# Voltmetr_MEZ.net
KiCad netlist of a schematic drawn in Altium Designer
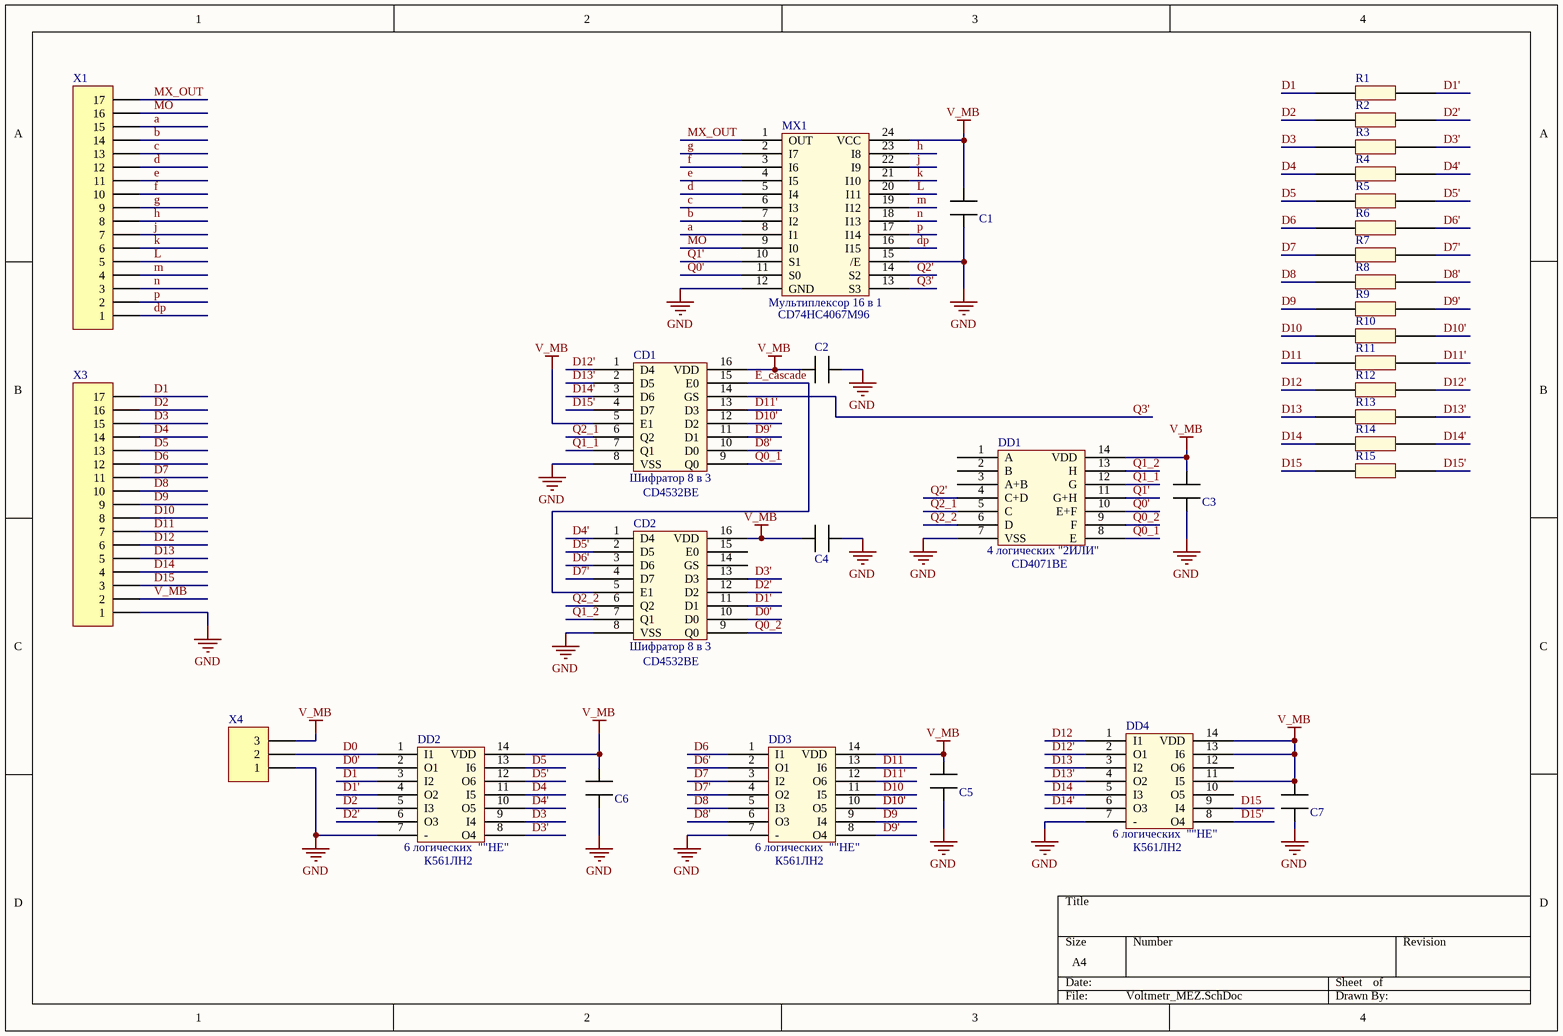
[diagram p0: Voltmetr_MEZ.SchDoc]

(export (version "E")
  (design (tool "Eeschema 10.0.6"))
  (components
    (comp (ref "C1")
      (value "CAP_SMALL")
      (footprint "CAP_SMALL")
      (libsource (lib "vpl_Schlib") (part "CAP_SMALL"))
    )
    (comp (ref "C2")
      (value "CAP_SMALL")
      (footprint "CAP_SMALL")
      (libsource (lib "vpl_Schlib") (part "CAP_SMALL"))
    )
    (comp (ref "C3")
      (value "CAP_SMALL")
      (footprint "CAP_SMALL")
      (libsource (lib "vpl_Schlib") (part "CAP_SMALL"))
    )
    (comp (ref "C4")
      (value "CAP_SMALL")
      (footprint "CAP_SMALL")
      (libsource (lib "vpl_Schlib") (part "CAP_SMALL"))
    )
    (comp (ref "C5")
      (value "CAP_SMALL")
      (footprint "CAP_SMALL")
      (libsource (lib "vpl_Schlib") (part "CAP_SMALL"))
    )
    (comp (ref "C6")
      (value "CAP_SMALL")
      (footprint "CAP_SMALL")
      (libsource (lib "vpl_Schlib") (part "CAP_SMALL"))
    )
    (comp (ref "C7")
      (value "CAP_SMALL")
      (footprint "CAP_SMALL")
      (libsource (lib "vpl_Schlib") (part "CAP_SMALL"))
    )
    (comp (ref "CD1")
      (value "CD4532BE")
      (footprint "DIP16_PANNEL")
      (description "Шифратор приоритетный 8 - 3 [DIP-16]")
      (libsource (lib "msp_SchLib") (part "CD4532BE"))
    )
    (comp (ref "CD2")
      (value "CD4532BE")
      (footprint "DIP16_PANNEL")
      (description "Шифратор приоритетный 8 - 3 [DIP-16]")
      (libsource (lib "msp_SchLib") (part "CD4532BE"))
    )
    (comp (ref "DD1")
      (value "CD4071BE")
      (footprint "Dip14_pannel")
      (description "Четыре логических элемента \"2ИЛИ\", [DIP-14]")
      (libsource (lib "msp_SchLib") (part "CD4071BE"))
    )
    (comp (ref "DD2")
      (value "К561ЛН2")
      (footprint "Dip14_pannel")
      (description "Шесть логических элементов \"HЕ\" (DIP-14)")
      (libsource (lib "msp_SchLib") (part "К561ЛН2"))
    )
    (comp (ref "DD3")
      (value "К561ЛН2")
      (footprint "Dip14_pannel")
      (description "Шесть логических элементов \"HЕ\" (DIP-14)")
      (libsource (lib "msp_SchLib") (part "К561ЛН2"))
    )
    (comp (ref "DD4")
      (value "К561ЛН2")
      (footprint "Dip14_pannel")
      (description "Шесть логических элементов \"HЕ\" (DIP-14)")
      (libsource (lib "msp_SchLib") (part "К561ЛН2"))
    )
    (comp (ref "MX1")
      (value "CD74HC4067M96")
      (footprint "SOIC-24")
      (description "16-и канальный аналоговый мультиплексор/ демультиплексор, [SO-24]")
      (libsource (lib "msp_SchLib") (part "CD74HC4067M96"))
    )
    (comp (ref "R1") (value "resistor") (footprint "RES 0805") (libsource (lib "msp_SchLib") (part "RES")))
    (comp (ref "R2") (value "resistor") (footprint "RES 0805") (libsource (lib "msp_SchLib") (part "RES")))
    (comp (ref "R3") (value "resistor") (footprint "RES 0805") (libsource (lib "msp_SchLib") (part "RES")))
    (comp (ref "R4") (value "resistor") (footprint "RES 0805") (libsource (lib "msp_SchLib") (part "RES")))
    (comp (ref "R5") (value "resistor") (footprint "RES 0805") (libsource (lib "msp_SchLib") (part "RES")))
    (comp (ref "R6") (value "resistor") (footprint "RES 0805") (libsource (lib "msp_SchLib") (part "RES")))
    (comp (ref "R7") (value "resistor") (footprint "RES 0805") (libsource (lib "msp_SchLib") (part "RES")))
    (comp (ref "R8") (value "resistor") (footprint "RES 0805") (libsource (lib "msp_SchLib") (part "RES")))
    (comp (ref "R9") (value "resistor") (footprint "RES 0805") (libsource (lib "msp_SchLib") (part "RES")))
    (comp (ref "R10") (value "resistor") (footprint "RES 0805") (libsource (lib "msp_SchLib") (part "RES")))
    (comp (ref "R11") (value "resistor") (footprint "RES 0805") (libsource (lib "msp_SchLib") (part "RES")))
    (comp (ref "R12") (value "resistor") (footprint "RES 0805") (libsource (lib "msp_SchLib") (part "RES")))
    (comp (ref "R13") (value "resistor") (footprint "RES 0805") (libsource (lib "msp_SchLib") (part "RES")))
    (comp (ref "R14") (value "resistor") (footprint "RES 0805") (libsource (lib "msp_SchLib") (part "RES")))
    (comp (ref "R15") (value "resistor") (footprint "RES 0805") (libsource (lib "msp_SchLib") (part "RES")))
    (comp (ref "X1")
      (value "Header 17")
      (footprint "HDR1X17")
      (description "Header, 17-Pin")
      (fields (field (name "PUBLISHER") "Altium Limited"))
      (libsource (lib "Miscellaneous Connectors") (part "Header 17"))
    )
    (comp (ref "X3")
      (value "Header 17")
      (footprint "HDR1X17")
      (description "Header, 17-Pin")
      (fields (field (name "PUBLISHER") "Altium Limited"))
      (libsource (lib "Miscellaneous Connectors") (part "Header 17"))
    )
    (comp (ref "X4")
      (value "Header 3")
      (footprint "HDR1X3")
      (description "Header, 3-Pin")
      (fields (field (name "PUBLISHER") "Altium Limited"))
      (libsource (lib "Miscellaneous Connectors") (part "Header 3"))
    )
  )
  (nets
    (net (code "2") (name "/D0") (class "Default")
      (node (ref "DD2") (pin "1") (pinfunction "I1_1") (pintype "passive"))
      (node (ref "X4") (pin "2") (pinfunction "2_2") (pintype "passive"))
    )
    (net (code "3") (name "/D0'") (class "Default")
      (node (ref "CD2") (pin "10") (pinfunction "D0_10") (pintype "passive"))
      (node (ref "DD2") (pin "2") (pinfunction "O1_2") (pintype "passive"))
    )
    (net (code "4") (name "/D1") (class "Default")
      (node (ref "DD2") (pin "3") (pinfunction "I2_3") (pintype "passive"))
      (node (ref "R1") (pin "1") (pinfunction "1_1") (pintype "passive"))
      (node (ref "X3") (pin "17") (pinfunction "17_17") (pintype "passive"))
    )
    (net (code "5") (name "/D1'") (class "Default")
      (node (ref "CD2") (pin "11") (pinfunction "D1_11") (pintype "passive"))
      (node (ref "DD2") (pin "4") (pinfunction "O2_4") (pintype "passive"))
      (node (ref "R1") (pin "2") (pinfunction "2_2") (pintype "passive"))
    )
    (net (code "6") (name "/D2") (class "Default")
      (node (ref "DD2") (pin "5") (pinfunction "I3_5") (pintype "passive"))
      (node (ref "R2") (pin "1") (pinfunction "1_1") (pintype "passive"))
      (node (ref "X3") (pin "16") (pinfunction "16_16") (pintype "passive"))
    )
    (net (code "7") (name "/D2'") (class "Default")
      (node (ref "CD2") (pin "12") (pinfunction "D2_12") (pintype "passive"))
      (node (ref "DD2") (pin "6") (pinfunction "O3_6") (pintype "passive"))
      (node (ref "R2") (pin "2") (pinfunction "2_2") (pintype "passive"))
    )
    (net (code "8") (name "/D3") (class "Default")
      (node (ref "DD2") (pin "9") (pinfunction "I4_9") (pintype "passive"))
      (node (ref "R3") (pin "1") (pinfunction "1_1") (pintype "passive"))
      (node (ref "X3") (pin "15") (pinfunction "15_15") (pintype "passive"))
    )
    (net (code "9") (name "/D3'") (class "Default")
      (node (ref "CD2") (pin "13") (pinfunction "D3_13") (pintype "passive"))
      (node (ref "DD2") (pin "8") (pinfunction "O4_8") (pintype "passive"))
      (node (ref "R3") (pin "2") (pinfunction "2_2") (pintype "passive"))
    )
    (net (code "10") (name "/D4") (class "Default")
      (node (ref "DD2") (pin "11") (pinfunction "I5_11") (pintype "passive"))
      (node (ref "R4") (pin "1") (pinfunction "1_1") (pintype "passive"))
      (node (ref "X3") (pin "14") (pinfunction "14_14") (pintype "passive"))
    )
    (net (code "11") (name "/D4'") (class "Default")
      (node (ref "CD2") (pin "1") (pinfunction "D4_1") (pintype "passive"))
      (node (ref "DD2") (pin "10") (pinfunction "O5_10") (pintype "passive"))
      (node (ref "R4") (pin "2") (pinfunction "2_2") (pintype "passive"))
    )
    (net (code "12") (name "/D5") (class "Default")
      (node (ref "DD2") (pin "13") (pinfunction "I6_13") (pintype "passive"))
      (node (ref "R5") (pin "1") (pinfunction "1_1") (pintype "passive"))
      (node (ref "X3") (pin "13") (pinfunction "13_13") (pintype "passive"))
    )
    (net (code "13") (name "/D5'") (class "Default")
      (node (ref "CD2") (pin "2") (pinfunction "D5_2") (pintype "passive"))
      (node (ref "DD2") (pin "12") (pinfunction "O6_12") (pintype "passive"))
      (node (ref "R5") (pin "2") (pinfunction "2_2") (pintype "passive"))
    )
    (net (code "14") (name "/D6") (class "Default")
      (node (ref "DD3") (pin "1") (pinfunction "I1_1") (pintype "passive"))
      (node (ref "R6") (pin "1") (pinfunction "1_1") (pintype "passive"))
      (node (ref "X3") (pin "12") (pinfunction "12_12") (pintype "passive"))
    )
    (net (code "15") (name "/D6'") (class "Default")
      (node (ref "CD2") (pin "3") (pinfunction "D6_3") (pintype "passive"))
      (node (ref "DD3") (pin "2") (pinfunction "O1_2") (pintype "passive"))
      (node (ref "R6") (pin "2") (pinfunction "2_2") (pintype "passive"))
    )
    (net (code "16") (name "/D7") (class "Default")
      (node (ref "DD3") (pin "3") (pinfunction "I2_3") (pintype "passive"))
      (node (ref "R7") (pin "1") (pinfunction "1_1") (pintype "passive"))
      (node (ref "X3") (pin "11") (pinfunction "11_11") (pintype "passive"))
    )
    (net (code "17") (name "/D7'") (class "Default")
      (node (ref "CD2") (pin "4") (pinfunction "D7_4") (pintype "passive"))
      (node (ref "DD3") (pin "4") (pinfunction "O2_4") (pintype "passive"))
      (node (ref "R7") (pin "2") (pinfunction "2_2") (pintype "passive"))
    )
    (net (code "18") (name "/D8") (class "Default")
      (node (ref "DD3") (pin "5") (pinfunction "I3_5") (pintype "passive"))
      (node (ref "R8") (pin "1") (pinfunction "1_1") (pintype "passive"))
      (node (ref "X3") (pin "10") (pinfunction "10_10") (pintype "passive"))
    )
    (net (code "19") (name "/D8'") (class "Default")
      (node (ref "CD1") (pin "10") (pinfunction "D0_10") (pintype "passive"))
      (node (ref "DD3") (pin "6") (pinfunction "O3_6") (pintype "passive"))
      (node (ref "R8") (pin "2") (pinfunction "2_2") (pintype "passive"))
    )
    (net (code "20") (name "/D9") (class "Default")
      (node (ref "DD3") (pin "9") (pinfunction "I4_9") (pintype "passive"))
      (node (ref "R9") (pin "1") (pinfunction "1_1") (pintype "passive"))
      (node (ref "X3") (pin "9") (pinfunction "9_9") (pintype "passive"))
    )
    (net (code "21") (name "/D9'") (class "Default")
      (node (ref "CD1") (pin "11") (pinfunction "D1_11") (pintype "passive"))
      (node (ref "DD3") (pin "8") (pinfunction "O4_8") (pintype "passive"))
      (node (ref "R9") (pin "2") (pinfunction "2_2") (pintype "passive"))
    )
    (net (code "22") (name "/D10") (class "Default")
      (node (ref "DD3") (pin "11") (pinfunction "I5_11") (pintype "passive"))
      (node (ref "R10") (pin "1") (pinfunction "1_1") (pintype "passive"))
      (node (ref "X3") (pin "8") (pinfunction "8_8") (pintype "passive"))
    )
    (net (code "23") (name "/D10'") (class "Default")
      (node (ref "CD1") (pin "12") (pinfunction "D2_12") (pintype "passive"))
      (node (ref "DD3") (pin "10") (pinfunction "O5_10") (pintype "passive"))
      (node (ref "R10") (pin "2") (pinfunction "2_2") (pintype "passive"))
    )
    (net (code "24") (name "/D11") (class "Default")
      (node (ref "DD3") (pin "13") (pinfunction "I6_13") (pintype "passive"))
      (node (ref "R11") (pin "1") (pinfunction "1_1") (pintype "passive"))
      (node (ref "X3") (pin "7") (pinfunction "7_7") (pintype "passive"))
    )
    (net (code "25") (name "/D11'") (class "Default")
      (node (ref "CD1") (pin "13") (pinfunction "D3_13") (pintype "passive"))
      (node (ref "DD3") (pin "12") (pinfunction "O6_12") (pintype "passive"))
      (node (ref "R11") (pin "2") (pinfunction "2_2") (pintype "passive"))
    )
    (net (code "26") (name "/D12") (class "Default")
      (node (ref "DD4") (pin "1") (pinfunction "I1_1") (pintype "passive"))
      (node (ref "R12") (pin "1") (pinfunction "1_1") (pintype "passive"))
      (node (ref "X3") (pin "6") (pinfunction "6_6") (pintype "passive"))
    )
    (net (code "27") (name "/D12'") (class "Default")
      (node (ref "CD1") (pin "1") (pinfunction "D4_1") (pintype "passive"))
      (node (ref "DD4") (pin "2") (pinfunction "O1_2") (pintype "passive"))
      (node (ref "R12") (pin "2") (pinfunction "2_2") (pintype "passive"))
    )
    (net (code "28") (name "/D13") (class "Default")
      (node (ref "DD4") (pin "3") (pinfunction "I2_3") (pintype "passive"))
      (node (ref "R13") (pin "1") (pinfunction "1_1") (pintype "passive"))
      (node (ref "X3") (pin "5") (pinfunction "5_5") (pintype "passive"))
    )
    (net (code "29") (name "/D13'") (class "Default")
      (node (ref "CD1") (pin "2") (pinfunction "D5_2") (pintype "passive"))
      (node (ref "DD4") (pin "4") (pinfunction "O2_4") (pintype "passive"))
      (node (ref "R13") (pin "2") (pinfunction "2_2") (pintype "passive"))
    )
    (net (code "30") (name "/D14") (class "Default")
      (node (ref "DD4") (pin "5") (pinfunction "I3_5") (pintype "passive"))
      (node (ref "R14") (pin "1") (pinfunction "1_1") (pintype "passive"))
      (node (ref "X3") (pin "4") (pinfunction "4_4") (pintype "passive"))
    )
    (net (code "31") (name "/D14'") (class "Default")
      (node (ref "CD1") (pin "3") (pinfunction "D6_3") (pintype "passive"))
      (node (ref "DD4") (pin "6") (pinfunction "O3_6") (pintype "passive"))
      (node (ref "R14") (pin "2") (pinfunction "2_2") (pintype "passive"))
    )
    (net (code "32") (name "/D15") (class "Default")
      (node (ref "DD4") (pin "9") (pinfunction "I4_9") (pintype "passive"))
      (node (ref "R15") (pin "1") (pinfunction "1_1") (pintype "passive"))
      (node (ref "X3") (pin "3") (pinfunction "3_3") (pintype "passive"))
    )
    (net (code "33") (name "/D15'") (class "Default")
      (node (ref "CD1") (pin "4") (pinfunction "D7_4") (pintype "passive"))
      (node (ref "DD4") (pin "8") (pinfunction "O4_8") (pintype "passive"))
      (node (ref "R15") (pin "2") (pinfunction "2_2") (pintype "passive"))
    )
    (net (code "34") (name "/E_cascade") (class "Default")
      (node (ref "CD1") (pin "15") (pinfunction "E0_15") (pintype "passive"))
      (node (ref "CD2") (pin "5") (pinfunction "E1_5") (pintype "passive"))
    )
    (net (code "35") (name "/L") (class "Default")
      (node (ref "MX1") (pin "20") (pinfunction "I11_20") (pintype "passive"))
      (node (ref "X1") (pin "5") (pinfunction "5_5") (pintype "passive"))
    )
    (net (code "36") (name "/MX_OUT") (class "Default")
      (node (ref "MX1") (pin "1") (pinfunction "OUT_1") (pintype "passive"))
      (node (ref "X1") (pin "17") (pinfunction "17_17") (pintype "passive"))
    )
    (net (code "37") (name "/Q0'") (class "Default")
      (node (ref "DD1") (pin "10") (pinfunction "E+F_10") (pintype "passive"))
      (node (ref "MX1") (pin "11") (pinfunction "S0_11") (pintype "passive"))
    )
    (net (code "38") (name "/Q0_1") (class "Default")
      (node (ref "CD1") (pin "9") (pinfunction "Q0_9") (pintype "passive"))
      (node (ref "DD1") (pin "8") (pinfunction "E_8") (pintype "passive"))
    )
    (net (code "39") (name "/Q0_2") (class "Default")
      (node (ref "CD2") (pin "9") (pinfunction "Q0_9") (pintype "passive"))
      (node (ref "DD1") (pin "9") (pinfunction "F_9") (pintype "passive"))
    )
    (net (code "40") (name "/Q1'") (class "Default")
      (node (ref "DD1") (pin "11") (pinfunction "G+H_11") (pintype "passive"))
      (node (ref "MX1") (pin "10") (pinfunction "S1_10") (pintype "passive"))
    )
    (net (code "41") (name "/Q1_1") (class "Default")
      (node (ref "CD1") (pin "7") (pinfunction "Q1_7") (pintype "passive"))
      (node (ref "DD1") (pin "12") (pinfunction "G_12") (pintype "passive"))
    )
    (net (code "42") (name "/Q1_2") (class "Default")
      (node (ref "CD2") (pin "7") (pinfunction "Q1_7") (pintype "passive"))
      (node (ref "DD1") (pin "13") (pinfunction "H_13") (pintype "passive"))
    )
    (net (code "43") (name "/Q2'") (class "Default")
      (node (ref "DD1") (pin "4") (pinfunction "C+D_4") (pintype "passive"))
      (node (ref "MX1") (pin "14") (pinfunction "S2_14") (pintype "passive"))
    )
    (net (code "44") (name "/Q2_1") (class "Default")
      (node (ref "CD1") (pin "6") (pinfunction "Q2_6") (pintype "passive"))
      (node (ref "DD1") (pin "5") (pinfunction "C_5") (pintype "passive"))
    )
    (net (code "45") (name "/Q2_2") (class "Default")
      (node (ref "CD2") (pin "6") (pinfunction "Q2_6") (pintype "passive"))
      (node (ref "DD1") (pin "6") (pinfunction "D_6") (pintype "passive"))
    )
    (net (code "46") (name "/Q3'") (class "Default")
      (node (ref "CD1") (pin "14") (pinfunction "GS_14") (pintype "passive"))
      (node (ref "MX1") (pin "13") (pinfunction "S3_13") (pintype "passive"))
    )
    (net (code "47") (name "/a") (class "Default")
      (node (ref "MX1") (pin "8") (pinfunction "I1_8") (pintype "passive"))
      (node (ref "X1") (pin "15") (pinfunction "15_15") (pintype "passive"))
    )
    (net (code "48") (name "/b") (class "Default")
      (node (ref "MX1") (pin "7") (pinfunction "I2_7") (pintype "passive"))
      (node (ref "X1") (pin "14") (pinfunction "14_14") (pintype "passive"))
    )
    (net (code "49") (name "/c") (class "Default")
      (node (ref "MX1") (pin "6") (pinfunction "I3_6") (pintype "passive"))
      (node (ref "X1") (pin "13") (pinfunction "13_13") (pintype "passive"))
    )
    (net (code "50") (name "/d") (class "Default")
      (node (ref "MX1") (pin "5") (pinfunction "I4_5") (pintype "passive"))
      (node (ref "X1") (pin "12") (pinfunction "12_12") (pintype "passive"))
    )
    (net (code "51") (name "/dp") (class "Default")
      (node (ref "MX1") (pin "16") (pinfunction "I15_16") (pintype "passive"))
      (node (ref "X1") (pin "1") (pinfunction "1_1") (pintype "passive"))
    )
    (net (code "52") (name "/e") (class "Default")
      (node (ref "MX1") (pin "4") (pinfunction "I5_4") (pintype "passive"))
      (node (ref "X1") (pin "11") (pinfunction "11_11") (pintype "passive"))
    )
    (net (code "53") (name "/f") (class "Default")
      (node (ref "MX1") (pin "3") (pinfunction "I6_3") (pintype "passive"))
      (node (ref "X1") (pin "10") (pinfunction "10_10") (pintype "passive"))
    )
    (net (code "54") (name "/g") (class "Default")
      (node (ref "MX1") (pin "2") (pinfunction "I7_2") (pintype "passive"))
      (node (ref "X1") (pin "9") (pinfunction "9_9") (pintype "passive"))
    )
    (net (code "55") (name "/h") (class "Default")
      (node (ref "MX1") (pin "23") (pinfunction "I8_23") (pintype "passive"))
      (node (ref "X1") (pin "8") (pinfunction "8_8") (pintype "passive"))
    )
    (net (code "56") (name "/j") (class "Default")
      (node (ref "MX1") (pin "22") (pinfunction "I9_22") (pintype "passive"))
      (node (ref "X1") (pin "7") (pinfunction "7_7") (pintype "passive"))
    )
    (net (code "57") (name "/k") (class "Default")
      (node (ref "MX1") (pin "21") (pinfunction "I10_21") (pintype "passive"))
      (node (ref "X1") (pin "6") (pinfunction "6_6") (pintype "passive"))
    )
    (net (code "58") (name "/m") (class "Default")
      (node (ref "MX1") (pin "19") (pinfunction "I12_19") (pintype "passive"))
      (node (ref "X1") (pin "4") (pinfunction "4_4") (pintype "passive"))
    )
    (net (code "59") (name "/n") (class "Default")
      (node (ref "MX1") (pin "18") (pinfunction "I13_18") (pintype "passive"))
      (node (ref "X1") (pin "3") (pinfunction "3_3") (pintype "passive"))
    )
    (net (code "60") (name "/p") (class "Default")
      (node (ref "MX1") (pin "17") (pinfunction "I14_17") (pintype "passive"))
      (node (ref "X1") (pin "2") (pinfunction "2_2") (pintype "passive"))
    )
    (net (code "61") (name "/~{MO}") (class "Default")
      (node (ref "MX1") (pin "9") (pinfunction "I0_9") (pintype "passive"))
      (node (ref "X1") (pin "16") (pinfunction "16_16") (pintype "passive"))
    )
    (net (code "62") (name "GND") (class "Default")
      (node (ref "C1") (pin "1") (pinfunction "1_1") (pintype "passive"))
      (node (ref "C2") (pin "2") (pinfunction "2_2") (pintype "passive"))
      (node (ref "C3") (pin "1") (pinfunction "1_1") (pintype "passive"))
      (node (ref "C4") (pin "1") (pinfunction "1_1") (pintype "passive"))
      (node (ref "C5") (pin "1") (pinfunction "1_1") (pintype "passive"))
      (node (ref "C6") (pin "1") (pinfunction "1_1") (pintype "passive"))
      (node (ref "C7") (pin "1") (pinfunction "1_1") (pintype "passive"))
      (node (ref "CD1") (pin "8") (pinfunction "VSS_8") (pintype "passive"))
      (node (ref "CD2") (pin "8") (pinfunction "VSS_8") (pintype "passive"))
      (node (ref "DD1") (pin "7") (pinfunction "VSS_7") (pintype "passive"))
      (node (ref "DD2") (pin "7") (pinfunction "-_7") (pintype "passive"))
      (node (ref "DD3") (pin "7") (pinfunction "-_7") (pintype "passive"))
      (node (ref "DD4") (pin "7") (pinfunction "-_7") (pintype "passive"))
      (node (ref "MX1") (pin "12") (pinfunction "GND_12") (pintype "passive"))
      (node (ref "MX1") (pin "15") (pinfunction "/E_15") (pintype "passive"))
      (node (ref "X3") (pin "1") (pinfunction "1_1") (pintype "passive"))
      (node (ref "X4") (pin "1") (pinfunction "1_1") (pintype "passive"))
    )
    (net (code "63") (name "V_MB") (class "Default")
      (node (ref "C1") (pin "2") (pinfunction "2_2") (pintype "passive"))
      (node (ref "C2") (pin "1") (pinfunction "1_1") (pintype "passive"))
      (node (ref "C3") (pin "2") (pinfunction "2_2") (pintype "passive"))
      (node (ref "C4") (pin "2") (pinfunction "2_2") (pintype "passive"))
      (node (ref "C5") (pin "2") (pinfunction "2_2") (pintype "passive"))
      (node (ref "C6") (pin "2") (pinfunction "2_2") (pintype "passive"))
      (node (ref "C7") (pin "2") (pinfunction "2_2") (pintype "passive"))
      (node (ref "CD1") (pin "16") (pinfunction "VDD_16") (pintype "passive"))
      (node (ref "CD1") (pin "5") (pinfunction "E1_5") (pintype "passive"))
      (node (ref "CD2") (pin "16") (pinfunction "VDD_16") (pintype "passive"))
      (node (ref "DD1") (pin "14") (pinfunction "VDD_14") (pintype "passive"))
      (node (ref "DD2") (pin "14") (pinfunction "VDD_14") (pintype "passive"))
      (node (ref "DD3") (pin "14") (pinfunction "VDD_14") (pintype "passive"))
      (node (ref "DD4") (pin "11") (pinfunction "I5_11") (pintype "passive"))
      (node (ref "DD4") (pin "13") (pinfunction "I6_13") (pintype "passive"))
      (node (ref "DD4") (pin "14") (pinfunction "VDD_14") (pintype "passive"))
      (node (ref "MX1") (pin "24") (pinfunction "VCC_24") (pintype "passive"))
      (node (ref "X3") (pin "2") (pinfunction "2_2") (pintype "passive"))
      (node (ref "X4") (pin "3") (pinfunction "3_3") (pintype "passive"))
    )
    (net (code "64") (name "unconnected-(CD2-E0-Pad15)") (class "Default")
      (node (ref "CD2") (pin "15") (pinfunction "E0_15") (pintype "passive"))
    )
    (net (code "65") (name "unconnected-(CD2-GS-Pad14)") (class "Default")
      (node (ref "CD2") (pin "14") (pinfunction "GS_14") (pintype "passive"))
    )
    (net (code "66") (name "unconnected-(DD1-A+B-Pad3)") (class "Default")
      (node (ref "DD1") (pin "3") (pinfunction "A+B_3") (pintype "passive"))
    )
    (net (code "67") (name "unconnected-(DD1-A-Pad1)") (class "Default")
      (node (ref "DD1") (pin "1") (pinfunction "A_1") (pintype "passive"))
    )
    (net (code "68") (name "unconnected-(DD1-B-Pad2)") (class "Default")
      (node (ref "DD1") (pin "2") (pinfunction "B_2") (pintype "passive"))
    )
    (net (code "69") (name "unconnected-(DD4-O5-Pad10)") (class "Default")
      (node (ref "DD4") (pin "10") (pinfunction "O5_10") (pintype "passive"))
    )
    (net (code "70") (name "unconnected-(DD4-O6-Pad12)") (class "Default")
      (node (ref "DD4") (pin "12") (pinfunction "O6_12") (pintype "passive"))
    )
  )
)
